# mpr-8x-mux.net
KiCad netlist of a schematic drawn in EAGLE
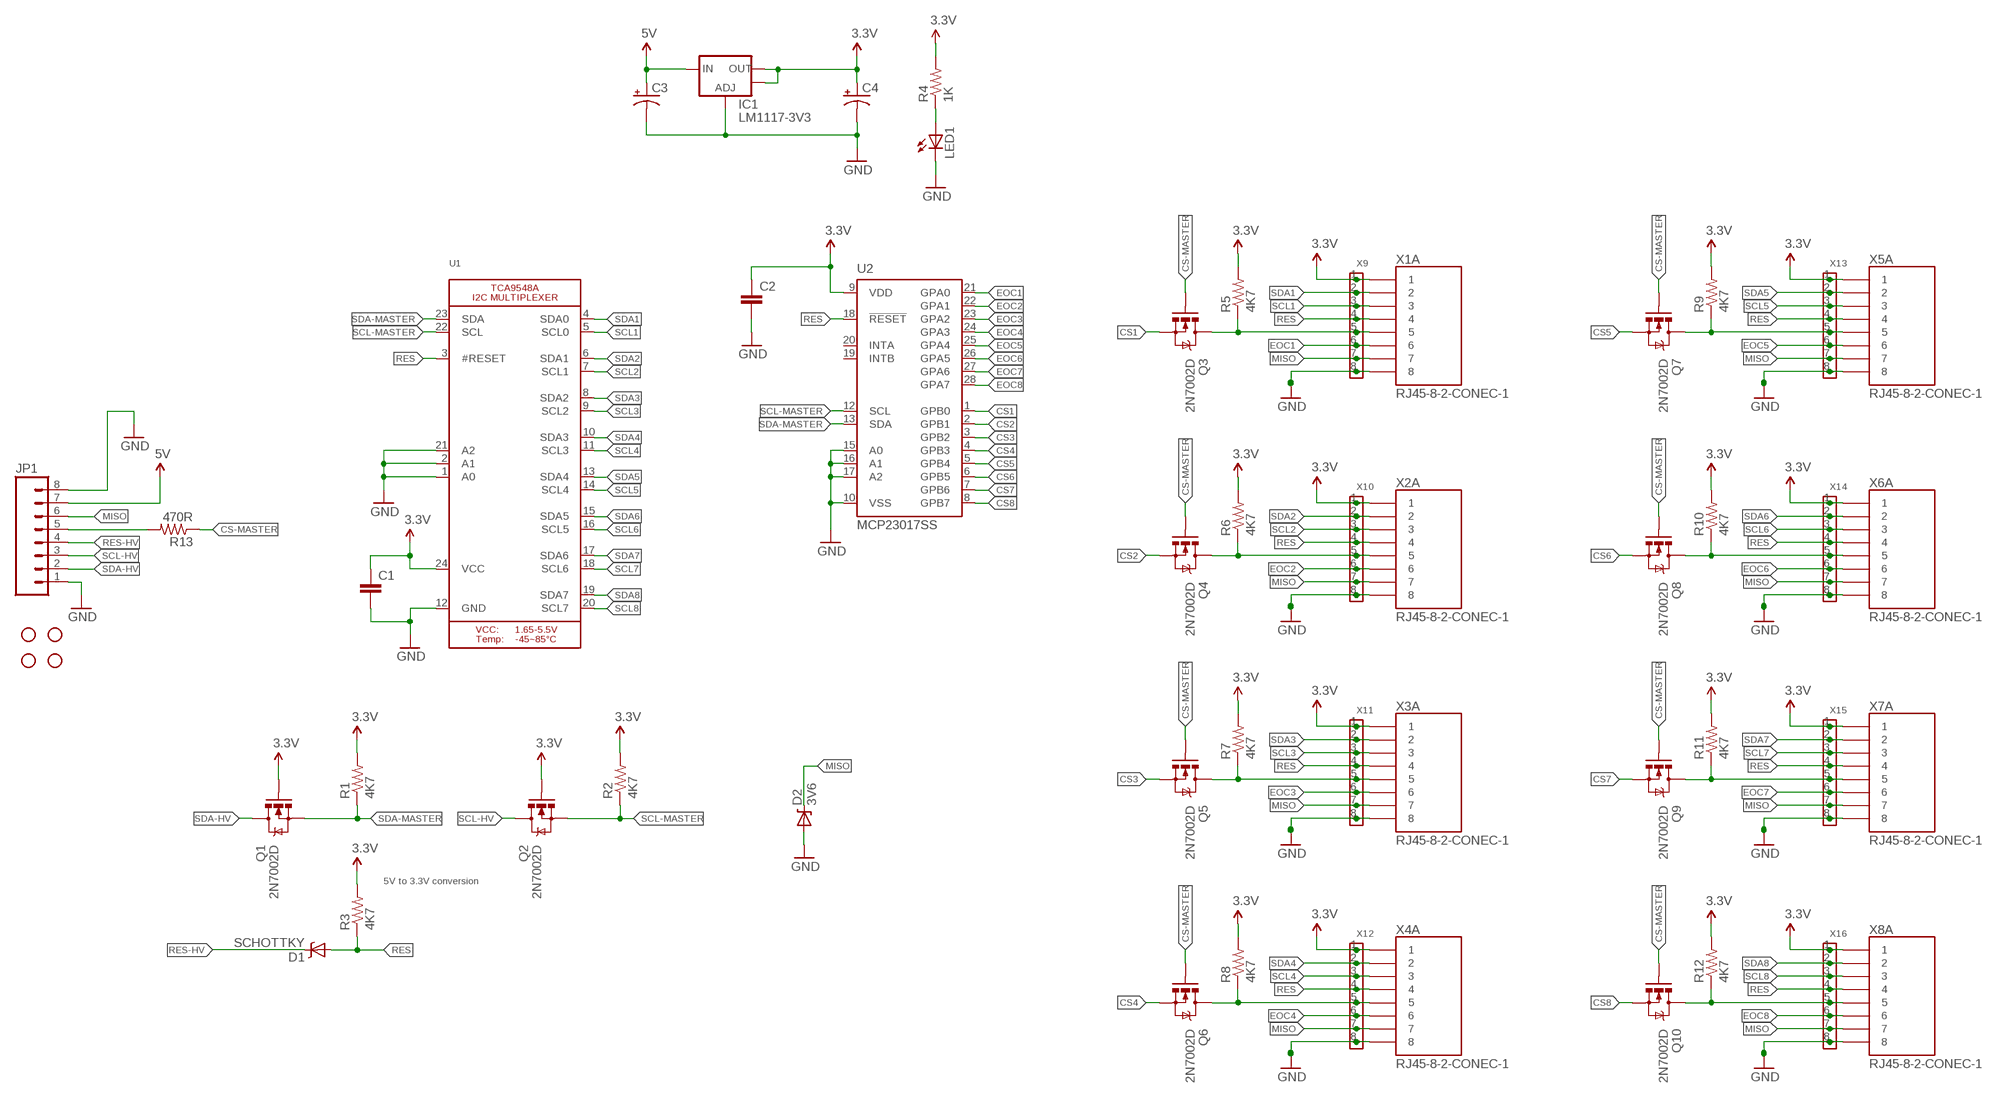
[diagram p0: schematic, sheet 1]

(export (version "E")
  (design (tool "Eeschema 10.0.6"))
  (components
    (comp (ref "C1")
      (value "CAP0805")
      (footprint "eagle-import:0805")
      (libsource (lib "eagle-import") (part "CAP0805"))
    )
    (comp (ref "C2")
      (value "CAP0805")
      (footprint "eagle-import:0805")
      (libsource (lib "eagle-import") (part "CAP0805"))
    )
    (comp (ref "C3")
      (value "CAP_POL1206-KIT")
      (footprint "eagle-import:EIA3216-KIT")
      (libsource (lib "eagle-import") (part "CAP_POL1206-KIT"))
    )
    (comp (ref "C4")
      (value "CAP_POL1206-KIT")
      (footprint "eagle-import:EIA3216-KIT")
      (libsource (lib "eagle-import") (part "CAP_POL1206-KIT"))
    )
    (comp (ref "D1")
      (value "SCHOTTKY")
      (footprint "eagle-import:SOD-323")
      (libsource (lib "eagle-import") (part "DIODE-SCHOTTKYSOD"))
    )
    (comp (ref "D2")
      (value "3V6")
      (footprint "eagle-import:SOD-323")
      (libsource (lib "eagle-import") (part "DIODE-ZENERSOD"))
    )
    (comp (ref "IC1")
      (value "LM1117-3V3")
      (footprint "eagle-import:SOT223")
      (libsource (lib "eagle-import") (part "V_REG_LM1117SOT223"))
    )
    (comp (ref "JP1")
      (value "M081X08")
      (footprint "eagle-import:1X08")
      (libsource (lib "eagle-import") (part "M081X08"))
    )
    (comp (ref "JP2")
      (value "STAND-OFF")
      (footprint "eagle-import:STAND-OFF")
      (libsource (lib "eagle-import") (part "STAND-OFF"))
    )
    (comp (ref "JP3")
      (value "STAND-OFF")
      (footprint "eagle-import:STAND-OFF")
      (libsource (lib "eagle-import") (part "STAND-OFF"))
    )
    (comp (ref "JP4")
      (value "STAND-OFF")
      (footprint "eagle-import:STAND-OFF")
      (libsource (lib "eagle-import") (part "STAND-OFF"))
    )
    (comp (ref "JP5")
      (value "STAND-OFF")
      (footprint "eagle-import:STAND-OFF")
      (libsource (lib "eagle-import") (part "STAND-OFF"))
    )
    (comp (ref "LED1")
      (value "LED0603")
      (footprint "eagle-import:LED-0603")
      (libsource (lib "eagle-import") (part "LED0603"))
    )
    (comp (ref "Q1")
      (value "2N7002D")
      (footprint "eagle-import:SOT23-3")
      (libsource (lib "eagle-import") (part "MOSFET-NCHANNELSMD"))
    )
    (comp (ref "Q2")
      (value "2N7002D")
      (footprint "eagle-import:SOT23-3")
      (libsource (lib "eagle-import") (part "MOSFET-NCHANNELSMD"))
    )
    (comp (ref "Q3")
      (value "2N7002D")
      (footprint "eagle-import:SOT23-3")
      (libsource (lib "eagle-import") (part "MOSFET-NCHANNELSMD"))
    )
    (comp (ref "Q4")
      (value "2N7002D")
      (footprint "eagle-import:SOT23-3")
      (libsource (lib "eagle-import") (part "MOSFET-NCHANNELSMD"))
    )
    (comp (ref "Q5")
      (value "2N7002D")
      (footprint "eagle-import:SOT23-3")
      (libsource (lib "eagle-import") (part "MOSFET-NCHANNELSMD"))
    )
    (comp (ref "Q6")
      (value "2N7002D")
      (footprint "eagle-import:SOT23-3")
      (libsource (lib "eagle-import") (part "MOSFET-NCHANNELSMD"))
    )
    (comp (ref "Q7")
      (value "2N7002D")
      (footprint "eagle-import:SOT23-3")
      (libsource (lib "eagle-import") (part "MOSFET-NCHANNELSMD"))
    )
    (comp (ref "Q8")
      (value "2N7002D")
      (footprint "eagle-import:SOT23-3")
      (libsource (lib "eagle-import") (part "MOSFET-NCHANNELSMD"))
    )
    (comp (ref "Q9")
      (value "2N7002D")
      (footprint "eagle-import:SOT23-3")
      (libsource (lib "eagle-import") (part "MOSFET-NCHANNELSMD"))
    )
    (comp (ref "Q10")
      (value "2N7002D")
      (footprint "eagle-import:SOT23-3")
      (libsource (lib "eagle-import") (part "MOSFET-NCHANNELSMD"))
    )
    (comp (ref "R1")
      (value "4K7")
      (footprint "eagle-import:0805")
      (libsource (lib "eagle-import") (part "RESISTOR0805-RES"))
    )
    (comp (ref "R2")
      (value "4K7")
      (footprint "eagle-import:0805")
      (libsource (lib "eagle-import") (part "RESISTOR0805-RES"))
    )
    (comp (ref "R3")
      (value "4K7")
      (footprint "eagle-import:0805")
      (libsource (lib "eagle-import") (part "RESISTOR0805-RES"))
    )
    (comp (ref "R4")
      (value "1K")
      (footprint "eagle-import:0805")
      (libsource (lib "eagle-import") (part "RESISTOR0805-RES"))
    )
    (comp (ref "R5")
      (value "4K7")
      (footprint "eagle-import:0805")
      (libsource (lib "eagle-import") (part "RESISTOR0805-RES"))
    )
    (comp (ref "R6")
      (value "4K7")
      (footprint "eagle-import:0805")
      (libsource (lib "eagle-import") (part "RESISTOR0805-RES"))
    )
    (comp (ref "R7")
      (value "4K7")
      (footprint "eagle-import:0805")
      (libsource (lib "eagle-import") (part "RESISTOR0805-RES"))
    )
    (comp (ref "R8")
      (value "4K7")
      (footprint "eagle-import:0805")
      (libsource (lib "eagle-import") (part "RESISTOR0805-RES"))
    )
    (comp (ref "R9")
      (value "4K7")
      (footprint "eagle-import:0805")
      (libsource (lib "eagle-import") (part "RESISTOR0805-RES"))
    )
    (comp (ref "R10")
      (value "4K7")
      (footprint "eagle-import:0805")
      (libsource (lib "eagle-import") (part "RESISTOR0805-RES"))
    )
    (comp (ref "R11")
      (value "4K7")
      (footprint "eagle-import:0805")
      (libsource (lib "eagle-import") (part "RESISTOR0805-RES"))
    )
    (comp (ref "R12")
      (value "4K7")
      (footprint "eagle-import:0805")
      (libsource (lib "eagle-import") (part "RESISTOR0805-RES"))
    )
    (comp (ref "R13")
      (value "470R")
      (footprint "eagle-import:0805")
      (libsource (lib "eagle-import") (part "RESISTOR0805-RES"))
    )
    (comp (ref "U1")
      (value "TCA9548A")
      (footprint "eagle-import:TSSOP24")
      (libsource (lib "eagle-import") (part "TCA9548A"))
    )
    (comp (ref "U2")
      (value "MCP23017SS")
      (footprint "eagle-import:SSOP28")
      (fields (field (name "MF") "MICROCHIP") (field (name "MPN") "MCP23017-E/SS"))
      (libsource (lib "eagle-import") (part "MCP23017SS"))
    )
    (comp (ref "X1")
      (value "RJ45-8-2-CONEC-1")
      (footprint "eagle-import:CONEC-33TS3004ST-88001")
      (libsource (lib "eagle-import") (part "RJ45-8-2-CONEC-1"))
    )
    (comp (ref "X2")
      (value "RJ45-8-2-CONEC-1")
      (footprint "eagle-import:CONEC-33TS3004ST-88001")
      (libsource (lib "eagle-import") (part "RJ45-8-2-CONEC-1"))
    )
    (comp (ref "X3")
      (value "RJ45-8-2-CONEC-1")
      (footprint "eagle-import:CONEC-33TS3004ST-88001")
      (libsource (lib "eagle-import") (part "RJ45-8-2-CONEC-1"))
    )
    (comp (ref "X4")
      (value "RJ45-8-2-CONEC-1")
      (footprint "eagle-import:CONEC-33TS3004ST-88001")
      (libsource (lib "eagle-import") (part "RJ45-8-2-CONEC-1"))
    )
    (comp (ref "X5")
      (value "RJ45-8-2-CONEC-1")
      (footprint "eagle-import:CONEC-33TS3004ST-88001")
      (libsource (lib "eagle-import") (part "RJ45-8-2-CONEC-1"))
    )
    (comp (ref "X6")
      (value "RJ45-8-2-CONEC-1")
      (footprint "eagle-import:CONEC-33TS3004ST-88001")
      (libsource (lib "eagle-import") (part "RJ45-8-2-CONEC-1"))
    )
    (comp (ref "X7")
      (value "RJ45-8-2-CONEC-1")
      (footprint "eagle-import:CONEC-33TS3004ST-88001")
      (libsource (lib "eagle-import") (part "RJ45-8-2-CONEC-1"))
    )
    (comp (ref "X8")
      (value "RJ45-8-2-CONEC-1")
      (footprint "eagle-import:CONEC-33TS3004ST-88001")
      (libsource (lib "eagle-import") (part "RJ45-8-2-CONEC-1"))
    )
    (comp (ref "X9")
      (value "TP-GROUP-X8-2X04")
      (footprint "eagle-import:2X4")
      (libsource (lib "eagle-import") (part "TP-GROUP-X8-2X04"))
    )
    (comp (ref "X10")
      (value "TP-GROUP-X8-2X04")
      (footprint "eagle-import:2X4")
      (libsource (lib "eagle-import") (part "TP-GROUP-X8-2X04"))
    )
    (comp (ref "X11")
      (value "TP-GROUP-X8-2X04")
      (footprint "eagle-import:2X4")
      (libsource (lib "eagle-import") (part "TP-GROUP-X8-2X04"))
    )
    (comp (ref "X12")
      (value "TP-GROUP-X8-2X04")
      (footprint "eagle-import:2X4")
      (libsource (lib "eagle-import") (part "TP-GROUP-X8-2X04"))
    )
    (comp (ref "X13")
      (value "TP-GROUP-X8-2X04")
      (footprint "eagle-import:2X4")
      (libsource (lib "eagle-import") (part "TP-GROUP-X8-2X04"))
    )
    (comp (ref "X14")
      (value "TP-GROUP-X8-2X04")
      (footprint "eagle-import:2X4")
      (libsource (lib "eagle-import") (part "TP-GROUP-X8-2X04"))
    )
    (comp (ref "X15")
      (value "TP-GROUP-X8-2X04")
      (footprint "eagle-import:2X4")
      (libsource (lib "eagle-import") (part "TP-GROUP-X8-2X04"))
    )
    (comp (ref "X16")
      (value "TP-GROUP-X8-2X04")
      (footprint "eagle-import:2X4")
      (libsource (lib "eagle-import") (part "TP-GROUP-X8-2X04"))
    )
  )
  (nets
    (net (code "1") (name "3.3V") (class "Default")
      (node (ref "C1") (pin "1") (pinfunction "1_1") (pintype "passive"))
      (node (ref "C2") (pin "1") (pinfunction "1_1") (pintype "passive"))
      (node (ref "C4") (pin "A") (pinfunction "+_A") (pintype "passive"))
      (node (ref "IC1") (pin "2") (pinfunction "OUT_2") (pintype "output"))
      (node (ref "IC1") (pin "4") (pinfunction "OUT_4") (pintype "output"))
      (node (ref "Q1") (pin "1") (pinfunction "G_1") (pintype "passive"))
      (node (ref "Q2") (pin "1") (pinfunction "G_1") (pintype "passive"))
      (node (ref "R1") (pin "2") (pinfunction "2_2") (pintype "passive"))
      (node (ref "R10") (pin "2") (pinfunction "2_2") (pintype "passive"))
      (node (ref "R11") (pin "2") (pinfunction "2_2") (pintype "passive"))
      (node (ref "R12") (pin "2") (pinfunction "2_2") (pintype "passive"))
      (node (ref "R2") (pin "2") (pinfunction "2_2") (pintype "passive"))
      (node (ref "R3") (pin "2") (pinfunction "2_2") (pintype "passive"))
      (node (ref "R4") (pin "2") (pinfunction "2_2") (pintype "passive"))
      (node (ref "R5") (pin "2") (pinfunction "2_2") (pintype "passive"))
      (node (ref "R6") (pin "2") (pinfunction "2_2") (pintype "passive"))
      (node (ref "R7") (pin "2") (pinfunction "2_2") (pintype "passive"))
      (node (ref "R8") (pin "2") (pinfunction "2_2") (pintype "passive"))
      (node (ref "R9") (pin "2") (pinfunction "2_2") (pintype "passive"))
      (node (ref "U1") (pin "24") (pinfunction "VCC_24") (pintype "bidirectional"))
      (node (ref "U2") (pin "9") (pinfunction "VDD_9") (pintype "power_in"))
      (node (ref "X1") (pin "1") (pinfunction "1_1") (pintype "bidirectional"))
      (node (ref "X10") (pin "1") (pinfunction "P$1_1") (pintype "bidirectional"))
      (node (ref "X11") (pin "1") (pinfunction "P$1_1") (pintype "bidirectional"))
      (node (ref "X12") (pin "1") (pinfunction "P$1_1") (pintype "bidirectional"))
      (node (ref "X13") (pin "1") (pinfunction "P$1_1") (pintype "bidirectional"))
      (node (ref "X14") (pin "1") (pinfunction "P$1_1") (pintype "bidirectional"))
      (node (ref "X15") (pin "1") (pinfunction "P$1_1") (pintype "bidirectional"))
      (node (ref "X16") (pin "1") (pinfunction "P$1_1") (pintype "bidirectional"))
      (node (ref "X2") (pin "1") (pinfunction "1_1") (pintype "bidirectional"))
      (node (ref "X3") (pin "1") (pinfunction "1_1") (pintype "bidirectional"))
      (node (ref "X4") (pin "1") (pinfunction "1_1") (pintype "bidirectional"))
      (node (ref "X5") (pin "1") (pinfunction "1_1") (pintype "bidirectional"))
      (node (ref "X6") (pin "1") (pinfunction "1_1") (pintype "bidirectional"))
      (node (ref "X7") (pin "1") (pinfunction "1_1") (pintype "bidirectional"))
      (node (ref "X8") (pin "1") (pinfunction "1_1") (pintype "bidirectional"))
      (node (ref "X9") (pin "1") (pinfunction "P$1_1") (pintype "bidirectional"))
    )
    (net (code "2") (name "5V") (class "Default")
      (node (ref "C3") (pin "A") (pinfunction "+_A") (pintype "passive"))
      (node (ref "IC1") (pin "3") (pinfunction "IN_3") (pintype "input"))
      (node (ref "JP1") (pin "7") (pinfunction "7_7") (pintype "passive"))
    )
    (net (code "3") (name "CS-MASTER") (class "Default")
      (node (ref "Q10") (pin "1") (pinfunction "G_1") (pintype "passive"))
      (node (ref "Q3") (pin "1") (pinfunction "G_1") (pintype "passive"))
      (node (ref "Q4") (pin "1") (pinfunction "G_1") (pintype "passive"))
      (node (ref "Q5") (pin "1") (pinfunction "G_1") (pintype "passive"))
      (node (ref "Q6") (pin "1") (pinfunction "G_1") (pintype "passive"))
      (node (ref "Q7") (pin "1") (pinfunction "G_1") (pintype "passive"))
      (node (ref "Q8") (pin "1") (pinfunction "G_1") (pintype "passive"))
      (node (ref "Q9") (pin "1") (pinfunction "G_1") (pintype "passive"))
      (node (ref "R13") (pin "1") (pinfunction "1_1") (pintype "passive"))
    )
    (net (code "4") (name "CS1") (class "Default")
      (node (ref "Q3") (pin "2") (pinfunction "S_2") (pintype "passive"))
      (node (ref "U2") (pin "1") (pinfunction "GPB0_1") (pintype "bidirectional"))
    )
    (net (code "5") (name "CS2") (class "Default")
      (node (ref "Q4") (pin "2") (pinfunction "S_2") (pintype "passive"))
      (node (ref "U2") (pin "2") (pinfunction "GPB1_2") (pintype "bidirectional"))
    )
    (net (code "6") (name "CS3") (class "Default")
      (node (ref "Q5") (pin "2") (pinfunction "S_2") (pintype "passive"))
      (node (ref "U2") (pin "3") (pinfunction "GPB2_3") (pintype "bidirectional"))
    )
    (net (code "7") (name "CS4") (class "Default")
      (node (ref "Q6") (pin "2") (pinfunction "S_2") (pintype "passive"))
      (node (ref "U2") (pin "4") (pinfunction "GPB3_4") (pintype "bidirectional"))
    )
    (net (code "8") (name "CS5") (class "Default")
      (node (ref "Q7") (pin "2") (pinfunction "S_2") (pintype "passive"))
      (node (ref "U2") (pin "5") (pinfunction "GPB4_5") (pintype "bidirectional"))
    )
    (net (code "9") (name "CS6") (class "Default")
      (node (ref "Q8") (pin "2") (pinfunction "S_2") (pintype "passive"))
      (node (ref "U2") (pin "6") (pinfunction "GPB5_6") (pintype "bidirectional"))
    )
    (net (code "10") (name "CS7") (class "Default")
      (node (ref "Q9") (pin "2") (pinfunction "S_2") (pintype "passive"))
      (node (ref "U2") (pin "7") (pinfunction "GPB6_7") (pintype "bidirectional"))
    )
    (net (code "11") (name "CS8") (class "Default")
      (node (ref "Q10") (pin "2") (pinfunction "S_2") (pintype "passive"))
      (node (ref "U2") (pin "8") (pinfunction "GPB7_8") (pintype "bidirectional"))
    )
    (net (code "12") (name "EOC1") (class "Default")
      (node (ref "U2") (pin "21") (pinfunction "GPA0_21") (pintype "bidirectional"))
      (node (ref "X1") (pin "6") (pinfunction "6_6") (pintype "bidirectional"))
      (node (ref "X9") (pin "6") (pinfunction "P$6_6") (pintype "bidirectional"))
    )
    (net (code "13") (name "EOC2") (class "Default")
      (node (ref "U2") (pin "22") (pinfunction "GPA1_22") (pintype "bidirectional"))
      (node (ref "X10") (pin "6") (pinfunction "P$6_6") (pintype "bidirectional"))
      (node (ref "X2") (pin "6") (pinfunction "6_6") (pintype "bidirectional"))
    )
    (net (code "14") (name "EOC3") (class "Default")
      (node (ref "U2") (pin "23") (pinfunction "GPA2_23") (pintype "bidirectional"))
      (node (ref "X11") (pin "6") (pinfunction "P$6_6") (pintype "bidirectional"))
      (node (ref "X3") (pin "6") (pinfunction "6_6") (pintype "bidirectional"))
    )
    (net (code "15") (name "EOC4") (class "Default")
      (node (ref "U2") (pin "24") (pinfunction "GPA3_24") (pintype "bidirectional"))
      (node (ref "X12") (pin "6") (pinfunction "P$6_6") (pintype "bidirectional"))
      (node (ref "X4") (pin "6") (pinfunction "6_6") (pintype "bidirectional"))
    )
    (net (code "16") (name "EOC5") (class "Default")
      (node (ref "U2") (pin "25") (pinfunction "GPA4_25") (pintype "bidirectional"))
      (node (ref "X13") (pin "6") (pinfunction "P$6_6") (pintype "bidirectional"))
      (node (ref "X5") (pin "6") (pinfunction "6_6") (pintype "bidirectional"))
    )
    (net (code "17") (name "EOC6") (class "Default")
      (node (ref "U2") (pin "26") (pinfunction "GPA5_26") (pintype "bidirectional"))
      (node (ref "X14") (pin "6") (pinfunction "P$6_6") (pintype "bidirectional"))
      (node (ref "X6") (pin "6") (pinfunction "6_6") (pintype "bidirectional"))
    )
    (net (code "18") (name "EOC7") (class "Default")
      (node (ref "U2") (pin "27") (pinfunction "GPA6_27") (pintype "bidirectional"))
      (node (ref "X15") (pin "6") (pinfunction "P$6_6") (pintype "bidirectional"))
      (node (ref "X7") (pin "6") (pinfunction "6_6") (pintype "bidirectional"))
    )
    (net (code "19") (name "EOC8") (class "Default")
      (node (ref "U2") (pin "28") (pinfunction "GPA7_28") (pintype "bidirectional"))
      (node (ref "X16") (pin "6") (pinfunction "P$6_6") (pintype "bidirectional"))
      (node (ref "X8") (pin "6") (pinfunction "6_6") (pintype "bidirectional"))
    )
    (net (code "20") (name "GND") (class "Default")
      (node (ref "C1") (pin "2") (pinfunction "2_2") (pintype "passive"))
      (node (ref "C2") (pin "2") (pinfunction "2_2") (pintype "passive"))
      (node (ref "C3") (pin "C") (pinfunction "-_C") (pintype "passive"))
      (node (ref "C4") (pin "C") (pinfunction "-_C") (pintype "passive"))
      (node (ref "D2") (pin "2") (pinfunction "A_2") (pintype "passive"))
      (node (ref "IC1") (pin "1") (pinfunction "ADJ_1") (pintype "input"))
      (node (ref "JP1") (pin "1") (pinfunction "1_1") (pintype "passive"))
      (node (ref "JP1") (pin "8") (pinfunction "8_8") (pintype "passive"))
      (node (ref "LED1") (pin "C") (pinfunction "C_C") (pintype "passive"))
      (node (ref "U1") (pin "1") (pinfunction "A0_1") (pintype "bidirectional"))
      (node (ref "U1") (pin "12") (pinfunction "GND_12") (pintype "bidirectional"))
      (node (ref "U1") (pin "2") (pinfunction "A1_2") (pintype "bidirectional"))
      (node (ref "U1") (pin "21") (pinfunction "A2_21") (pintype "bidirectional"))
      (node (ref "U2") (pin "10") (pinfunction "VSS_10") (pintype "power_in"))
      (node (ref "U2") (pin "15") (pinfunction "A0_15") (pintype "input"))
      (node (ref "U2") (pin "16") (pinfunction "A1_16") (pintype "input"))
      (node (ref "U2") (pin "17") (pinfunction "A2_17") (pintype "input"))
      (node (ref "X1") (pin "8") (pinfunction "8_8") (pintype "bidirectional"))
      (node (ref "X1") (pin "M1") (pinfunction "P$1_M1") (pintype "bidirectional"))
      (node (ref "X1") (pin "M2") (pinfunction "P$1_M2") (pintype "bidirectional"))
      (node (ref "X10") (pin "8") (pinfunction "P$8_8") (pintype "bidirectional"))
      (node (ref "X11") (pin "8") (pinfunction "P$8_8") (pintype "bidirectional"))
      (node (ref "X12") (pin "8") (pinfunction "P$8_8") (pintype "bidirectional"))
      (node (ref "X13") (pin "8") (pinfunction "P$8_8") (pintype "bidirectional"))
      (node (ref "X14") (pin "8") (pinfunction "P$8_8") (pintype "bidirectional"))
      (node (ref "X15") (pin "8") (pinfunction "P$8_8") (pintype "bidirectional"))
      (node (ref "X16") (pin "8") (pinfunction "P$8_8") (pintype "bidirectional"))
      (node (ref "X2") (pin "8") (pinfunction "8_8") (pintype "bidirectional"))
      (node (ref "X2") (pin "M1") (pinfunction "P$1_M1") (pintype "bidirectional"))
      (node (ref "X2") (pin "M2") (pinfunction "P$1_M2") (pintype "bidirectional"))
      (node (ref "X3") (pin "8") (pinfunction "8_8") (pintype "bidirectional"))
      (node (ref "X3") (pin "M1") (pinfunction "P$1_M1") (pintype "bidirectional"))
      (node (ref "X3") (pin "M2") (pinfunction "P$1_M2") (pintype "bidirectional"))
      (node (ref "X4") (pin "8") (pinfunction "8_8") (pintype "bidirectional"))
      (node (ref "X4") (pin "M1") (pinfunction "P$1_M1") (pintype "bidirectional"))
      (node (ref "X4") (pin "M2") (pinfunction "P$1_M2") (pintype "bidirectional"))
      (node (ref "X5") (pin "8") (pinfunction "8_8") (pintype "bidirectional"))
      (node (ref "X5") (pin "M1") (pinfunction "P$1_M1") (pintype "bidirectional"))
      (node (ref "X5") (pin "M2") (pinfunction "P$1_M2") (pintype "bidirectional"))
      (node (ref "X6") (pin "8") (pinfunction "8_8") (pintype "bidirectional"))
      (node (ref "X6") (pin "M1") (pinfunction "P$1_M1") (pintype "bidirectional"))
      (node (ref "X6") (pin "M2") (pinfunction "P$1_M2") (pintype "bidirectional"))
      (node (ref "X7") (pin "8") (pinfunction "8_8") (pintype "bidirectional"))
      (node (ref "X7") (pin "M1") (pinfunction "P$1_M1") (pintype "bidirectional"))
      (node (ref "X7") (pin "M2") (pinfunction "P$1_M2") (pintype "bidirectional"))
      (node (ref "X8") (pin "8") (pinfunction "8_8") (pintype "bidirectional"))
      (node (ref "X8") (pin "M1") (pinfunction "P$1_M1") (pintype "bidirectional"))
      (node (ref "X8") (pin "M2") (pinfunction "P$1_M2") (pintype "bidirectional"))
      (node (ref "X9") (pin "8") (pinfunction "P$8_8") (pintype "bidirectional"))
    )
    (net (code "21") (name "MISO") (class "Default")
      (node (ref "D2") (pin "1") (pinfunction "C_1") (pintype "passive"))
      (node (ref "JP1") (pin "6") (pinfunction "6_6") (pintype "passive"))
      (node (ref "X1") (pin "7") (pinfunction "7_7") (pintype "bidirectional"))
      (node (ref "X10") (pin "7") (pinfunction "P$7_7") (pintype "bidirectional"))
      (node (ref "X11") (pin "7") (pinfunction "P$7_7") (pintype "bidirectional"))
      (node (ref "X12") (pin "7") (pinfunction "P$7_7") (pintype "bidirectional"))
      (node (ref "X13") (pin "7") (pinfunction "P$7_7") (pintype "bidirectional"))
      (node (ref "X14") (pin "7") (pinfunction "P$7_7") (pintype "bidirectional"))
      (node (ref "X15") (pin "7") (pinfunction "P$7_7") (pintype "bidirectional"))
      (node (ref "X16") (pin "7") (pinfunction "P$7_7") (pintype "bidirectional"))
      (node (ref "X2") (pin "7") (pinfunction "7_7") (pintype "bidirectional"))
      (node (ref "X3") (pin "7") (pinfunction "7_7") (pintype "bidirectional"))
      (node (ref "X4") (pin "7") (pinfunction "7_7") (pintype "bidirectional"))
      (node (ref "X5") (pin "7") (pinfunction "7_7") (pintype "bidirectional"))
      (node (ref "X6") (pin "7") (pinfunction "7_7") (pintype "bidirectional"))
      (node (ref "X7") (pin "7") (pinfunction "7_7") (pintype "bidirectional"))
      (node (ref "X8") (pin "7") (pinfunction "7_7") (pintype "bidirectional"))
      (node (ref "X9") (pin "7") (pinfunction "P$7_7") (pintype "bidirectional"))
    )
    (net (code "22") (name "Net-(JP1-Pad5)") (class "Default")
      (node (ref "JP1") (pin "5") (pinfunction "5_5") (pintype "passive"))
      (node (ref "R13") (pin "2") (pinfunction "2_2") (pintype "passive"))
    )
    (net (code "23") (name "Net-(LED1-PadA)") (class "Default")
      (node (ref "LED1") (pin "A") (pinfunction "A_A") (pintype "passive"))
      (node (ref "R4") (pin "1") (pinfunction "1_1") (pintype "passive"))
    )
    (net (code "24") (name "Net-(Q3-D)") (class "Default")
      (node (ref "Q3") (pin "3") (pinfunction "D_3") (pintype "passive"))
      (node (ref "R5") (pin "1") (pinfunction "1_1") (pintype "passive"))
      (node (ref "X1") (pin "5") (pinfunction "5_5") (pintype "bidirectional"))
      (node (ref "X9") (pin "5") (pinfunction "P$5_5") (pintype "bidirectional"))
    )
    (net (code "25") (name "Net-(Q4-D)") (class "Default")
      (node (ref "Q4") (pin "3") (pinfunction "D_3") (pintype "passive"))
      (node (ref "R6") (pin "1") (pinfunction "1_1") (pintype "passive"))
      (node (ref "X10") (pin "5") (pinfunction "P$5_5") (pintype "bidirectional"))
      (node (ref "X2") (pin "5") (pinfunction "5_5") (pintype "bidirectional"))
    )
    (net (code "26") (name "Net-(Q5-D)") (class "Default")
      (node (ref "Q5") (pin "3") (pinfunction "D_3") (pintype "passive"))
      (node (ref "R7") (pin "1") (pinfunction "1_1") (pintype "passive"))
      (node (ref "X11") (pin "5") (pinfunction "P$5_5") (pintype "bidirectional"))
      (node (ref "X3") (pin "5") (pinfunction "5_5") (pintype "bidirectional"))
    )
    (net (code "27") (name "Net-(Q6-D)") (class "Default")
      (node (ref "Q6") (pin "3") (pinfunction "D_3") (pintype "passive"))
      (node (ref "R8") (pin "1") (pinfunction "1_1") (pintype "passive"))
      (node (ref "X12") (pin "5") (pinfunction "P$5_5") (pintype "bidirectional"))
      (node (ref "X4") (pin "5") (pinfunction "5_5") (pintype "bidirectional"))
    )
    (net (code "28") (name "Net-(Q7-D)") (class "Default")
      (node (ref "Q7") (pin "3") (pinfunction "D_3") (pintype "passive"))
      (node (ref "R9") (pin "1") (pinfunction "1_1") (pintype "passive"))
      (node (ref "X13") (pin "5") (pinfunction "P$5_5") (pintype "bidirectional"))
      (node (ref "X5") (pin "5") (pinfunction "5_5") (pintype "bidirectional"))
    )
    (net (code "29") (name "Net-(Q8-D)") (class "Default")
      (node (ref "Q8") (pin "3") (pinfunction "D_3") (pintype "passive"))
      (node (ref "R10") (pin "1") (pinfunction "1_1") (pintype "passive"))
      (node (ref "X14") (pin "5") (pinfunction "P$5_5") (pintype "bidirectional"))
      (node (ref "X6") (pin "5") (pinfunction "5_5") (pintype "bidirectional"))
    )
    (net (code "30") (name "Net-(Q9-D)") (class "Default")
      (node (ref "Q9") (pin "3") (pinfunction "D_3") (pintype "passive"))
      (node (ref "R11") (pin "1") (pinfunction "1_1") (pintype "passive"))
      (node (ref "X15") (pin "5") (pinfunction "P$5_5") (pintype "bidirectional"))
      (node (ref "X7") (pin "5") (pinfunction "5_5") (pintype "bidirectional"))
    )
    (net (code "31") (name "Net-(Q10-D)") (class "Default")
      (node (ref "Q10") (pin "3") (pinfunction "D_3") (pintype "passive"))
      (node (ref "R12") (pin "1") (pinfunction "1_1") (pintype "passive"))
      (node (ref "X16") (pin "5") (pinfunction "P$5_5") (pintype "bidirectional"))
      (node (ref "X8") (pin "5") (pinfunction "5_5") (pintype "bidirectional"))
    )
    (net (code "32") (name "RES") (class "Default")
      (node (ref "D1") (pin "2") (pinfunction "A_2") (pintype "passive"))
      (node (ref "R3") (pin "1") (pinfunction "1_1") (pintype "passive"))
      (node (ref "U1") (pin "3") (pinfunction "#RESET_3") (pintype "bidirectional"))
      (node (ref "U2") (pin "18") (pinfunction "~{RESET}_18") (pintype "input"))
      (node (ref "X1") (pin "4") (pinfunction "4_4") (pintype "bidirectional"))
      (node (ref "X10") (pin "4") (pinfunction "P$4_4") (pintype "bidirectional"))
      (node (ref "X11") (pin "4") (pinfunction "P$4_4") (pintype "bidirectional"))
      (node (ref "X12") (pin "4") (pinfunction "P$4_4") (pintype "bidirectional"))
      (node (ref "X13") (pin "4") (pinfunction "P$4_4") (pintype "bidirectional"))
      (node (ref "X14") (pin "4") (pinfunction "P$4_4") (pintype "bidirectional"))
      (node (ref "X15") (pin "4") (pinfunction "P$4_4") (pintype "bidirectional"))
      (node (ref "X16") (pin "4") (pinfunction "P$4_4") (pintype "bidirectional"))
      (node (ref "X2") (pin "4") (pinfunction "4_4") (pintype "bidirectional"))
      (node (ref "X3") (pin "4") (pinfunction "4_4") (pintype "bidirectional"))
      (node (ref "X4") (pin "4") (pinfunction "4_4") (pintype "bidirectional"))
      (node (ref "X5") (pin "4") (pinfunction "4_4") (pintype "bidirectional"))
      (node (ref "X6") (pin "4") (pinfunction "4_4") (pintype "bidirectional"))
      (node (ref "X7") (pin "4") (pinfunction "4_4") (pintype "bidirectional"))
      (node (ref "X8") (pin "4") (pinfunction "4_4") (pintype "bidirectional"))
      (node (ref "X9") (pin "4") (pinfunction "P$4_4") (pintype "bidirectional"))
    )
    (net (code "33") (name "RES-HV") (class "Default")
      (node (ref "D1") (pin "1") (pinfunction "C_1") (pintype "passive"))
      (node (ref "JP1") (pin "4") (pinfunction "4_4") (pintype "passive"))
    )
    (net (code "34") (name "SCL-HV") (class "Default")
      (node (ref "JP1") (pin "3") (pinfunction "3_3") (pintype "passive"))
      (node (ref "Q2") (pin "3") (pinfunction "D_3") (pintype "passive"))
    )
    (net (code "35") (name "SCL-MASTER") (class "Default")
      (node (ref "Q2") (pin "2") (pinfunction "S_2") (pintype "passive"))
      (node (ref "R2") (pin "1") (pinfunction "1_1") (pintype "passive"))
      (node (ref "U1") (pin "22") (pinfunction "SCL_22") (pintype "bidirectional"))
      (node (ref "U2") (pin "12") (pinfunction "SCL_12") (pintype "input"))
    )
    (net (code "36") (name "SCL1") (class "Default")
      (node (ref "U1") (pin "5") (pinfunction "SCL0_5") (pintype "bidirectional"))
      (node (ref "X1") (pin "3") (pinfunction "3_3") (pintype "bidirectional"))
      (node (ref "X9") (pin "3") (pinfunction "P$3_3") (pintype "bidirectional"))
    )
    (net (code "37") (name "SCL2") (class "Default")
      (node (ref "U1") (pin "7") (pinfunction "SCL1_7") (pintype "bidirectional"))
      (node (ref "X10") (pin "3") (pinfunction "P$3_3") (pintype "bidirectional"))
      (node (ref "X2") (pin "3") (pinfunction "3_3") (pintype "bidirectional"))
    )
    (net (code "38") (name "SCL3") (class "Default")
      (node (ref "U1") (pin "9") (pinfunction "SCL2_9") (pintype "bidirectional"))
      (node (ref "X11") (pin "3") (pinfunction "P$3_3") (pintype "bidirectional"))
      (node (ref "X3") (pin "3") (pinfunction "3_3") (pintype "bidirectional"))
    )
    (net (code "39") (name "SCL4") (class "Default")
      (node (ref "U1") (pin "11") (pinfunction "SCL3_11") (pintype "bidirectional"))
      (node (ref "X12") (pin "3") (pinfunction "P$3_3") (pintype "bidirectional"))
      (node (ref "X4") (pin "3") (pinfunction "3_3") (pintype "bidirectional"))
    )
    (net (code "40") (name "SCL5") (class "Default")
      (node (ref "U1") (pin "14") (pinfunction "SCL4_14") (pintype "bidirectional"))
      (node (ref "X13") (pin "3") (pinfunction "P$3_3") (pintype "bidirectional"))
      (node (ref "X5") (pin "3") (pinfunction "3_3") (pintype "bidirectional"))
    )
    (net (code "41") (name "SCL6") (class "Default")
      (node (ref "U1") (pin "16") (pinfunction "SCL5_16") (pintype "bidirectional"))
      (node (ref "X14") (pin "3") (pinfunction "P$3_3") (pintype "bidirectional"))
      (node (ref "X6") (pin "3") (pinfunction "3_3") (pintype "bidirectional"))
    )
    (net (code "42") (name "SCL7") (class "Default")
      (node (ref "U1") (pin "18") (pinfunction "SCL6_18") (pintype "bidirectional"))
      (node (ref "X15") (pin "3") (pinfunction "P$3_3") (pintype "bidirectional"))
      (node (ref "X7") (pin "3") (pinfunction "3_3") (pintype "bidirectional"))
    )
    (net (code "43") (name "SCL8") (class "Default")
      (node (ref "U1") (pin "20") (pinfunction "SCL7_20") (pintype "bidirectional"))
      (node (ref "X16") (pin "3") (pinfunction "P$3_3") (pintype "bidirectional"))
      (node (ref "X8") (pin "3") (pinfunction "3_3") (pintype "bidirectional"))
    )
    (net (code "44") (name "SDA-HV") (class "Default")
      (node (ref "JP1") (pin "2") (pinfunction "2_2") (pintype "passive"))
      (node (ref "Q1") (pin "3") (pinfunction "D_3") (pintype "passive"))
    )
    (net (code "45") (name "SDA-MASTER") (class "Default")
      (node (ref "Q1") (pin "2") (pinfunction "S_2") (pintype "passive"))
      (node (ref "R1") (pin "1") (pinfunction "1_1") (pintype "passive"))
      (node (ref "U1") (pin "23") (pinfunction "SDA_23") (pintype "bidirectional"))
      (node (ref "U2") (pin "13") (pinfunction "SDA_13") (pintype "bidirectional"))
    )
    (net (code "46") (name "SDA1") (class "Default")
      (node (ref "U1") (pin "4") (pinfunction "SDA0_4") (pintype "bidirectional"))
      (node (ref "X1") (pin "2") (pinfunction "2_2") (pintype "bidirectional"))
      (node (ref "X9") (pin "2") (pinfunction "P$2_2") (pintype "bidirectional"))
    )
    (net (code "47") (name "SDA2") (class "Default")
      (node (ref "U1") (pin "6") (pinfunction "SDA1_6") (pintype "bidirectional"))
      (node (ref "X10") (pin "2") (pinfunction "P$2_2") (pintype "bidirectional"))
      (node (ref "X2") (pin "2") (pinfunction "2_2") (pintype "bidirectional"))
    )
    (net (code "48") (name "SDA3") (class "Default")
      (node (ref "U1") (pin "8") (pinfunction "SDA2_8") (pintype "bidirectional"))
      (node (ref "X11") (pin "2") (pinfunction "P$2_2") (pintype "bidirectional"))
      (node (ref "X3") (pin "2") (pinfunction "2_2") (pintype "bidirectional"))
    )
    (net (code "49") (name "SDA4") (class "Default")
      (node (ref "U1") (pin "10") (pinfunction "SDA3_10") (pintype "bidirectional"))
      (node (ref "X12") (pin "2") (pinfunction "P$2_2") (pintype "bidirectional"))
      (node (ref "X4") (pin "2") (pinfunction "2_2") (pintype "bidirectional"))
    )
    (net (code "50") (name "SDA5") (class "Default")
      (node (ref "U1") (pin "13") (pinfunction "SDA4_13") (pintype "bidirectional"))
      (node (ref "X13") (pin "2") (pinfunction "P$2_2") (pintype "bidirectional"))
      (node (ref "X5") (pin "2") (pinfunction "2_2") (pintype "bidirectional"))
    )
    (net (code "51") (name "SDA6") (class "Default")
      (node (ref "U1") (pin "15") (pinfunction "SDA5_15") (pintype "bidirectional"))
      (node (ref "X14") (pin "2") (pinfunction "P$2_2") (pintype "bidirectional"))
      (node (ref "X6") (pin "2") (pinfunction "2_2") (pintype "bidirectional"))
    )
    (net (code "52") (name "SDA7") (class "Default")
      (node (ref "U1") (pin "17") (pinfunction "SDA6_17") (pintype "bidirectional"))
      (node (ref "X15") (pin "2") (pinfunction "P$2_2") (pintype "bidirectional"))
      (node (ref "X7") (pin "2") (pinfunction "2_2") (pintype "bidirectional"))
    )
    (net (code "53") (name "SDA8") (class "Default")
      (node (ref "U1") (pin "19") (pinfunction "SDA7_19") (pintype "bidirectional"))
      (node (ref "X16") (pin "2") (pinfunction "P$2_2") (pintype "bidirectional"))
      (node (ref "X8") (pin "2") (pinfunction "2_2") (pintype "bidirectional"))
    )
    (net (code "54") (name "unconnected-(U2-INTA-Pad20)") (class "Default")
      (node (ref "U2") (pin "20") (pinfunction "INTA_20") (pintype "output"))
    )
    (net (code "55") (name "unconnected-(U2-INTB-Pad19)") (class "Default")
      (node (ref "U2") (pin "19") (pinfunction "INTB_19") (pintype "output"))
    )
  )
)
